# smart-pedal-routed.net
KiCad netlist of a schematic drawn in EAGLE
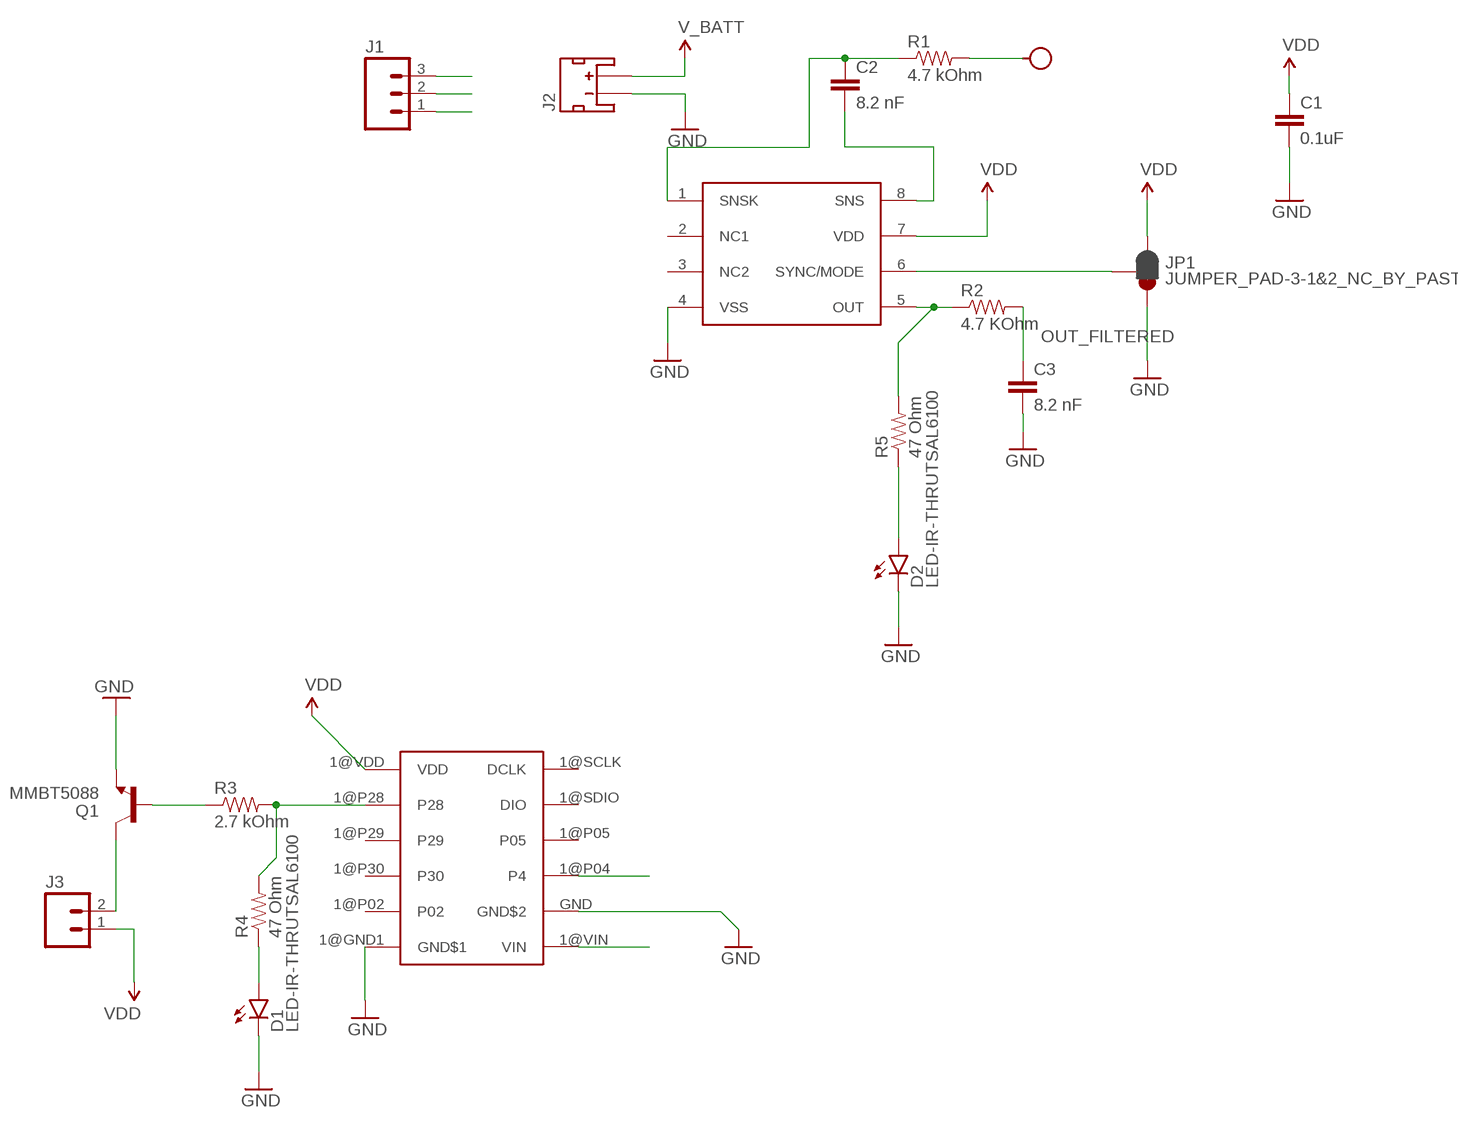
[diagram p0: schematic, sheet 1]

(export (version "E")
  (design (tool "Eeschema 10.0.6"))
  (components
    (comp (ref "C1")
      (value "0.1uF")
      (footprint "eagle-import:0603-CAP")
      (libsource (lib "eagle-import") (part "0.1UF-25V(+80/-20%)(0603)"))
    )
    (comp (ref "C2")
      (value "8.2 nF")
      (footprint "eagle-import:0603-CAP")
      (libsource (lib "eagle-import") (part "CAP0603-CAP"))
    )
    (comp (ref "C3")
      (value "8.2 nF")
      (footprint "eagle-import:0603-CAP")
      (libsource (lib "eagle-import") (part "CAP0603-CAP"))
    )
    (comp (ref "D1")
      (value "LED-IR-THRUTSAL6100")
      (footprint "eagle-import:LED5MM")
      (libsource (lib "eagle-import") (part "LED-IR-THRUTSAL6100"))
    )
    (comp (ref "D2")
      (value "LED-IR-THRUTSAL6100")
      (footprint "eagle-import:LED5MM")
      (libsource (lib "eagle-import") (part "LED-IR-THRUTSAL6100"))
    )
    (comp (ref "H1")
      (value "SEW_HOLE-SMALL")
      (footprint "eagle-import:SIMPLE_HOLE_SM")
      (libsource (lib "eagle-import") (part "SEW_HOLE-SMALL"))
    )
    (comp (ref "J1")
      (value "M03LOCK")
      (footprint "eagle-import:1X03_LOCK")
      (libsource (lib "eagle-import") (part "M03LOCK"))
    )
    (comp (ref "J2")
      (value "JST_2MM_MALE")
      (footprint "eagle-import:JST-2-SMD")
      (libsource (lib "eagle-import") (part "JST_2MM_MALE"))
    )
    (comp (ref "J3")
      (value "M02LOCK")
      (footprint "eagle-import:1X02_LOCK")
      (libsource (lib "eagle-import") (part "M02LOCK"))
    )
    (comp (ref "JP1")
      (value "JUMPER_PAD-3-1&2_NC_BY_PASTE")
      (footprint "eagle-import:PAD-HUMPER-3-1&2_NC_BY_PASTE_YES_SILK_FULL_BOX")
      (libsource (lib "eagle-import") (part "JUMPER_PAD-3-1&2_NC_BY_PASTE"))
    )
    (comp (ref "Q1")
      (value "MMBT5088")
      (footprint "eagle-import:SOT23-3")
      (libsource (lib "eagle-import") (part "TRANSISTOR_NPNMMBT5088"))
    )
    (comp (ref "R1")
      (value "4.7 kOhm")
      (footprint "eagle-import:0603-RES")
      (libsource (lib "eagle-import") (part "RESISTOR0603-RES"))
    )
    (comp (ref "R2")
      (value "4.7 KOhm")
      (footprint "eagle-import:0603-RES")
      (fields (field (name "SPICEPREFIX") "R"))
      (libsource (lib "eagle-import") (part "RESISTOR0603-RES"))
    )
    (comp (ref "R3")
      (value "2.7 kOhm")
      (footprint "eagle-import:0603-RES")
      (libsource (lib "eagle-import") (part "RESISTOR0603-RES"))
    )
    (comp (ref "R4")
      (value "47 Ohm")
      (footprint "eagle-import:0603-RES")
      (libsource (lib "eagle-import") (part "RESISTOR0603-RES"))
    )
    (comp (ref "R5")
      (value "47 Ohm")
      (footprint "eagle-import:0603-RES")
      (libsource (lib "eagle-import") (part "RESISTOR0603-RES"))
    )
    (comp (ref "U$1")
      (value "AT42QT1011")
      (footprint "eagle-import:UDFN8")
      (libsource (lib "eagle-import") (part "AT42QT1011"))
    )
    (comp (ref "U$2")
      (value "NANOV2")
      (footprint "eagle-import:NANOV2")
      (libsource (lib "eagle-import") (part "NANOV2"))
    )
  )
  (nets
    (net (code "1") (name "/MOTOR_OUT") (class "Default")
      (node (ref "J1") (pin "3") (pinfunction "3_3") (pintype "passive"))
      (node (ref "R3") (pin "2") (pinfunction "2_2") (pintype "passive"))
      (node (ref "R4") (pin "2") (pinfunction "2_2") (pintype "passive"))
      (node (ref "U$2") (pin "1@P28") (pinfunction "P28_1@P28") (pintype "bidirectional"))
    )
    (net (code "2") (name "/OUT_FILTERED") (class "Default")
      (node (ref "C3") (pin "1") (pinfunction "1_1") (pintype "passive"))
      (node (ref "J1") (pin "2") (pinfunction "2_2") (pintype "passive"))
      (node (ref "R2") (pin "2") (pinfunction "2_2") (pintype "passive"))
      (node (ref "U$2") (pin "1@P04") (pinfunction "P4_1@P04") (pintype "bidirectional"))
    )
    (net (code "3") (name "GND") (class "Default")
      (node (ref "C1") (pin "2") (pinfunction "2_2") (pintype "passive"))
      (node (ref "C3") (pin "2") (pinfunction "2_2") (pintype "passive"))
      (node (ref "D1") (pin "K") (pinfunction "C_K") (pintype "passive"))
      (node (ref "D2") (pin "K") (pinfunction "C_K") (pintype "passive"))
      (node (ref "J1") (pin "1") (pinfunction "1_1") (pintype "passive"))
      (node (ref "J2") (pin "1") (pinfunction "-_1") (pintype "bidirectional"))
      (node (ref "JP1") (pin "3") (pinfunction "3_3") (pintype "passive"))
      (node (ref "Q1") (pin "2") (pinfunction "E_2") (pintype "passive"))
      (node (ref "U$1") (pin "4") (pinfunction "VSS_4") (pintype "bidirectional"))
      (node (ref "U$2") (pin "1@GND1") (pinfunction "GND$1_1@GND1") (pintype "bidirectional"))
      (node (ref "U$2") (pin "GND") (pinfunction "GND$2_GND") (pintype "bidirectional"))
    )
    (net (code "4") (name "Net-(D1-PadA)") (class "Default")
      (node (ref "D1") (pin "A") (pinfunction "A_A") (pintype "passive"))
      (node (ref "R4") (pin "1") (pinfunction "1_1") (pintype "passive"))
    )
    (net (code "5") (name "Net-(D2-PadA)") (class "Default")
      (node (ref "D2") (pin "A") (pinfunction "A_A") (pintype "passive"))
      (node (ref "R5") (pin "1") (pinfunction "1_1") (pintype "passive"))
    )
    (net (code "6") (name "Net-(H1-PadP$1)") (class "Default")
      (node (ref "H1") (pin "P$1") (pinfunction "P$1_P$1") (pintype "bidirectional"))
      (node (ref "R1") (pin "2") (pinfunction "2_2") (pintype "passive"))
    )
    (net (code "7") (name "Net-(Q1-B)") (class "Default")
      (node (ref "Q1") (pin "1") (pinfunction "B_1") (pintype "passive"))
      (node (ref "R3") (pin "1") (pinfunction "1_1") (pintype "passive"))
    )
    (net (code "8") (name "Net-(Q1-C)") (class "Default")
      (node (ref "J3") (pin "2") (pinfunction "2_2") (pintype "passive"))
      (node (ref "Q1") (pin "3") (pinfunction "C_3") (pintype "passive"))
    )
    (net (code "9") (name "Net-(U$1-OUT)") (class "Default")
      (node (ref "R2") (pin "1") (pinfunction "1_1") (pintype "passive"))
      (node (ref "R5") (pin "2") (pinfunction "2_2") (pintype "passive"))
      (node (ref "U$1") (pin "5") (pinfunction "OUT_5") (pintype "bidirectional"))
    )
    (net (code "10") (name "Net-(U$1-SNS)") (class "Default")
      (node (ref "C2") (pin "2") (pinfunction "2_2") (pintype "passive"))
      (node (ref "U$1") (pin "8") (pinfunction "SNS_8") (pintype "bidirectional"))
    )
    (net (code "11") (name "Net-(U$1-SNSK)") (class "Default")
      (node (ref "C2") (pin "1") (pinfunction "1_1") (pintype "passive"))
      (node (ref "R1") (pin "1") (pinfunction "1_1") (pintype "passive"))
      (node (ref "U$1") (pin "1") (pinfunction "SNSK_1") (pintype "bidirectional"))
    )
    (net (code "12") (name "Net-(U$1-SYNC{slash}MODE)") (class "Default")
      (node (ref "JP1") (pin "2") (pinfunction "2_2") (pintype "passive"))
      (node (ref "U$1") (pin "6") (pinfunction "SYNC/MODE_6") (pintype "bidirectional"))
    )
    (net (code "13") (name "VDD") (class "Default")
      (node (ref "C1") (pin "1") (pinfunction "1_1") (pintype "passive"))
      (node (ref "J3") (pin "1") (pinfunction "1_1") (pintype "passive"))
      (node (ref "JP1") (pin "1") (pinfunction "1_1") (pintype "passive"))
      (node (ref "U$1") (pin "7") (pinfunction "VDD_7") (pintype "bidirectional"))
      (node (ref "U$2") (pin "1@VDD") (pinfunction "VDD_1@VDD") (pintype "bidirectional"))
    )
    (net (code "14") (name "V_BATT") (class "Default")
      (node (ref "J2") (pin "2") (pinfunction "+_2") (pintype "bidirectional"))
      (node (ref "U$2") (pin "1@VIN") (pinfunction "VIN_1@VIN") (pintype "bidirectional"))
    )
    (net (code "15") (name "unconnected-(J2-PAD1-PadNC1)") (class "Default")
      (node (ref "J2") (pin "NC1") (pinfunction "PAD1_NC1") (pintype "bidirectional"))
    )
    (net (code "16") (name "unconnected-(J2-PAD2-PadNC2)") (class "Default")
      (node (ref "J2") (pin "NC2") (pinfunction "PAD2_NC2") (pintype "bidirectional"))
    )
    (net (code "17") (name "unconnected-(U$1-NC1-Pad2)") (class "Default")
      (node (ref "U$1") (pin "2") (pinfunction "NC1_2") (pintype "bidirectional"))
    )
    (net (code "18") (name "unconnected-(U$1-NC2-Pad3)") (class "Default")
      (node (ref "U$1") (pin "3") (pinfunction "NC2_3") (pintype "bidirectional"))
    )
    (net (code "19") (name "unconnected-(U$2-DCLK-Pad1@SCLK)") (class "Default")
      (node (ref "U$2") (pin "1@SCLK") (pinfunction "DCLK_1@SCLK") (pintype "bidirectional"))
    )
    (net (code "20") (name "unconnected-(U$2-DIO-Pad1@SDIO)") (class "Default")
      (node (ref "U$2") (pin "1@SDIO") (pinfunction "DIO_1@SDIO") (pintype "bidirectional"))
    )
    (net (code "21") (name "unconnected-(U$2-P02-Pad1@P02)") (class "Default")
      (node (ref "U$2") (pin "1@P02") (pinfunction "P02_1@P02") (pintype "bidirectional"))
    )
    (net (code "22") (name "unconnected-(U$2-P05-Pad1@P05)") (class "Default")
      (node (ref "U$2") (pin "1@P05") (pinfunction "P05_1@P05") (pintype "bidirectional"))
    )
    (net (code "23") (name "unconnected-(U$2-P29-Pad1@P29)") (class "Default")
      (node (ref "U$2") (pin "1@P29") (pinfunction "P29_1@P29") (pintype "bidirectional"))
    )
    (net (code "24") (name "unconnected-(U$2-P30-Pad1@P30)") (class "Default")
      (node (ref "U$2") (pin "1@P30") (pinfunction "P30_1@P30") (pintype "bidirectional"))
    )
  )
)
